# PUSH-BUTTON_ENCODER.net
KiCad netlist of a schematic drawn in Altium Designer
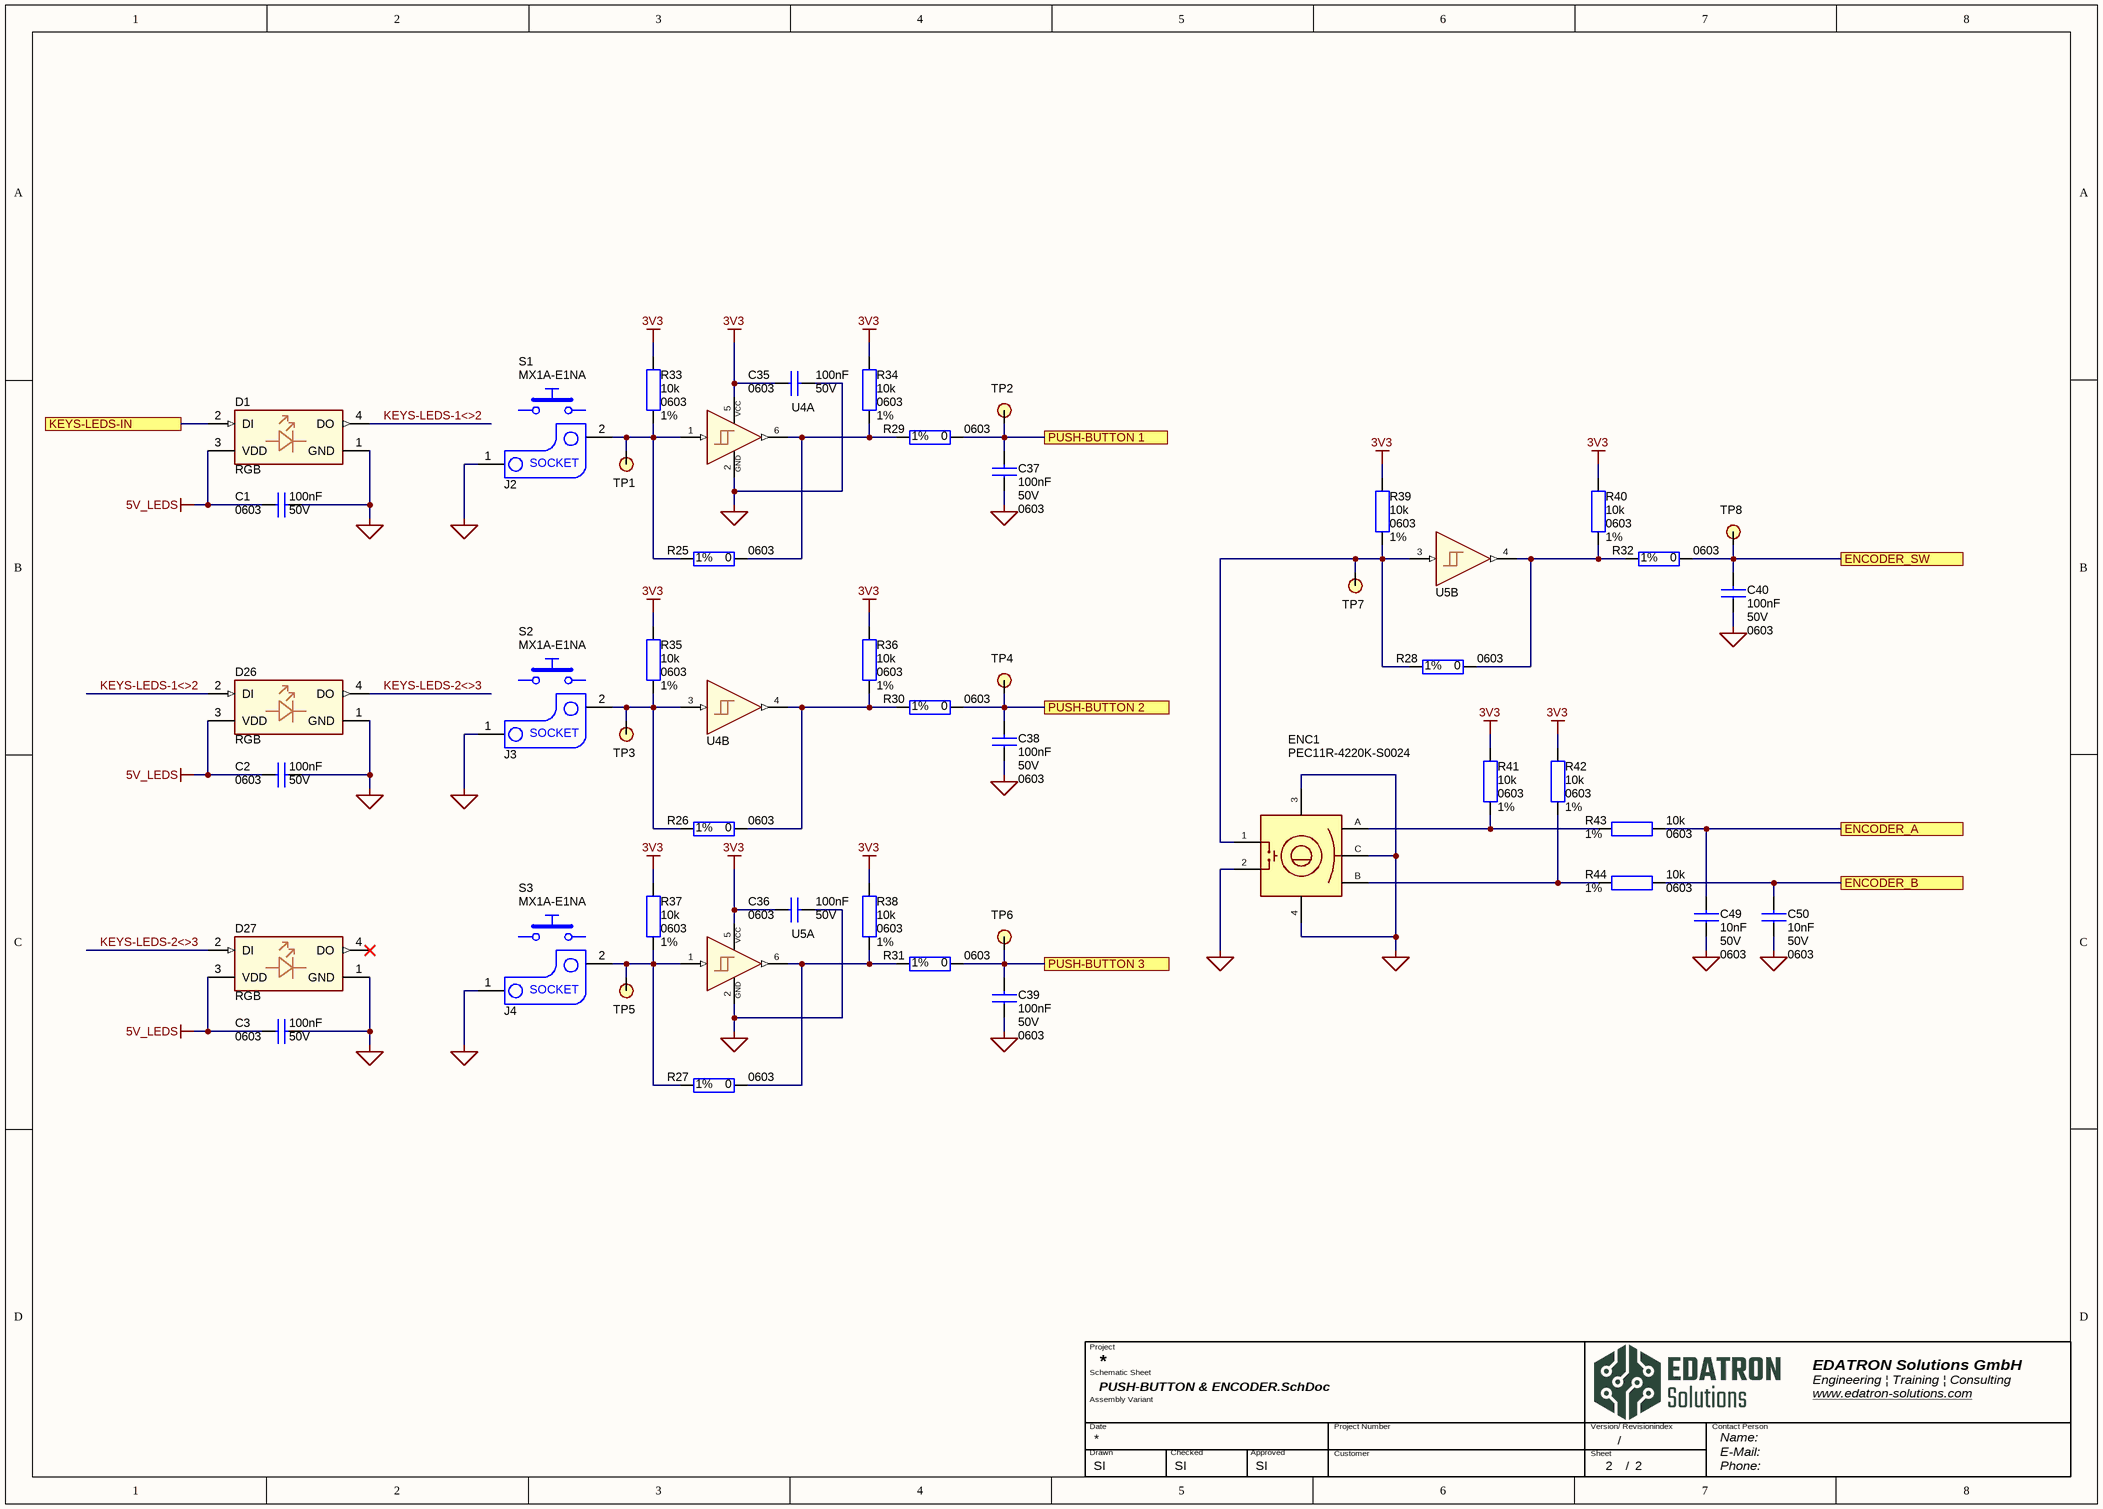
[diagram p0: PUSH-BUTTON & ENCODER.SchDoc]

(export (version "E")
  (design (tool "Eeschema 10.0.6"))
  (components
    (comp (ref "C1")
      (value "100nF")
      (footprint "CAPC0603X37L")
      (description "CAPACITOR 100 nF 0603 X7R 50V 10%")
      (fields
        (field (name "VOLTAGE") "50V")
        (field (name "MANUFACTURER 1 PART NUMBER") "C0603C104K5RACTU")
        (field (name "TOLERANCE") "10%")
        (field (name "CASE/PACKAGE") "0603")
        (field (name "COMMENT DESIGNER") "can be substituted same values other manufacturer")
      )
      (libsource (lib "EDATRON Solutions GmbH") (part "C"))
    )
    (comp (ref "C2")
      (value "100nF")
      (footprint "CAPC0603X37L")
      (description "CAPACITOR 100 nF 0603 X7R 50V 10%")
      (fields
        (field (name "VOLTAGE") "50V")
        (field (name "MANUFACTURER 1 PART NUMBER") "C0603C104K5RACTU")
        (field (name "TOLERANCE") "10%")
        (field (name "CASE/PACKAGE") "0603")
        (field (name "COMMENT DESIGNER") "can be substituted same values other manufacturer")
      )
      (libsource (lib "EDATRON Solutions GmbH") (part "C"))
    )
    (comp (ref "C3")
      (value "100nF")
      (footprint "CAPC0603X37L")
      (description "CAPACITOR 100 nF 0603 X7R 50V 10%")
      (fields
        (field (name "VOLTAGE") "50V")
        (field (name "MANUFACTURER 1 PART NUMBER") "C0603C104K5RACTU")
        (field (name "TOLERANCE") "10%")
        (field (name "CASE/PACKAGE") "0603")
        (field (name "COMMENT DESIGNER") "can be substituted same values other manufacturer")
      )
      (libsource (lib "EDATRON Solutions GmbH") (part "C"))
    )
    (comp (ref "C35")
      (value "100nF")
      (footprint "CAPC0603X37L")
      (description "CAPACITOR 100 nF 0603 X7R 50V 10%")
      (fields
        (field (name "VOLTAGE") "50V")
        (field (name "MANUFACTURER 1 PART NUMBER") "C0603C104K5RACTU")
        (field (name "TOLERANCE") "10%")
        (field (name "CASE/PACKAGE") "0603")
        (field (name "COMMENT DESIGNER") "can be substituted same values other manufacturer")
      )
      (libsource (lib "EDATRON Solutions GmbH") (part "C"))
    )
    (comp (ref "C36")
      (value "100nF")
      (footprint "CAPC0603X37L")
      (description "CAPACITOR 100 nF 0603 X7R 50V 10%")
      (fields
        (field (name "VOLTAGE") "50V")
        (field (name "MANUFACTURER 1 PART NUMBER") "C0603C104K5RACTU")
        (field (name "TOLERANCE") "10%")
        (field (name "CASE/PACKAGE") "0603")
        (field (name "COMMENT DESIGNER") "can be substituted same values other manufacturer")
      )
      (libsource (lib "EDATRON Solutions GmbH") (part "C"))
    )
    (comp (ref "C37")
      (value "100nF")
      (footprint "CAPC0603X37L")
      (description "CAPACITOR 100 nF 0603 X7R 50V 10%")
      (fields
        (field (name "VOLTAGE") "50V")
        (field (name "MANUFACTURER 1 PART NUMBER") "C0603C104K5RACTU")
        (field (name "TOLERANCE") "10%")
        (field (name "CASE/PACKAGE") "0603")
        (field (name "COMMENT DESIGNER") "can be substituted same values other manufacturer")
      )
      (libsource (lib "EDATRON Solutions GmbH") (part "C"))
    )
    (comp (ref "C38")
      (value "100nF")
      (footprint "CAPC0603X37L")
      (description "CAPACITOR 100 nF 0603 X7R 50V 10%")
      (fields
        (field (name "VOLTAGE") "50V")
        (field (name "MANUFACTURER 1 PART NUMBER") "C0603C104K5RACTU")
        (field (name "TOLERANCE") "10%")
        (field (name "CASE/PACKAGE") "0603")
        (field (name "COMMENT DESIGNER") "can be substituted same values other manufacturer")
      )
      (libsource (lib "EDATRON Solutions GmbH") (part "C"))
    )
    (comp (ref "C39")
      (value "100nF")
      (footprint "CAPC0603X37L")
      (description "CAPACITOR 100 nF 0603 X7R 50V 10%")
      (fields
        (field (name "VOLTAGE") "50V")
        (field (name "MANUFACTURER 1 PART NUMBER") "C0603C104K5RACTU")
        (field (name "TOLERANCE") "10%")
        (field (name "CASE/PACKAGE") "0603")
        (field (name "COMMENT DESIGNER") "can be substituted same values other manufacturer")
      )
      (libsource (lib "EDATRON Solutions GmbH") (part "C"))
    )
    (comp (ref "C40")
      (value "100nF")
      (footprint "CAPC0603X37L")
      (description "CAPACITOR 100 nF 0603 X7R 50V 10%")
      (fields
        (field (name "VOLTAGE") "50V")
        (field (name "MANUFACTURER 1 PART NUMBER") "C0603C104K5RACTU")
        (field (name "TOLERANCE") "10%")
        (field (name "CASE/PACKAGE") "0603")
        (field (name "COMMENT DESIGNER") "can be substituted same values other manufacturer")
      )
      (libsource (lib "EDATRON Solutions GmbH") (part "C"))
    )
    (comp (ref "C49")
      (value "10nF")
      (footprint "CAPC0603X37L")
      (description "CAPACITOR 10 nF 0603 X7R 50V 10%")
      (fields
        (field (name "VOLTAGE") "50V")
        (field (name "MANUFACTURER 1 PART NUMBER") "C0603C103K5RACTU")
        (field (name "TOLERANCE") "10%")
        (field (name "CASE/PACKAGE") "0603")
        (field (name "COMMENT DESIGNER") "can be substituted same values other manufacturer")
      )
      (libsource (lib "EDATRON Solutions GmbH") (part "C"))
    )
    (comp (ref "C50")
      (value "10nF")
      (footprint "CAPC0603X37L")
      (description "CAPACITOR 10 nF 0603 X7R 50V 10%")
      (fields
        (field (name "VOLTAGE") "50V")
        (field (name "MANUFACTURER 1 PART NUMBER") "C0603C103K5RACTU")
        (field (name "TOLERANCE") "10%")
        (field (name "CASE/PACKAGE") "0603")
        (field (name "COMMENT DESIGNER") "can be substituted same values other manufacturer")
      )
      (libsource (lib "EDATRON Solutions GmbH") (part "C"))
    )
    (comp (ref "D1")
      (value "SK6812MINI-E-012")
      (footprint "OPSCO_SK6812MINI-E-012")
      (description "SMD RGB LEDs(Built-in IC) ROHS  - Reverse Mount")
      (fields (field (name "COLOR") "RGB") (field (name "VOLTAGE") "5V"))
      (libsource (lib "EDATRON Solutions GmbH") (part "RGB-LED (Built-in IC) - Opsco"))
    )
    (comp (ref "D26")
      (value "SK6812MINI-E-012")
      (footprint "OPSCO_SK6812MINI-E-012")
      (description "SMD RGB LEDs(Built-in IC) ROHS  - Reverse Mount")
      (fields (field (name "COLOR") "RGB") (field (name "VOLTAGE") "5V"))
      (libsource (lib "EDATRON Solutions GmbH") (part "RGB-LED (Built-in IC) - Opsco"))
    )
    (comp (ref "D27")
      (value "SK6812MINI-E-012")
      (footprint "OPSCO_SK6812MINI-E-012")
      (description "SMD RGB LEDs(Built-in IC) ROHS  - Reverse Mount")
      (fields (field (name "COLOR") "RGB") (field (name "VOLTAGE") "5V"))
      (libsource (lib "EDATRON Solutions GmbH") (part "RGB-LED (Built-in IC) - Opsco"))
    )
    (comp (ref "ENC1")
      (value "PEC11R-4220K-S0024")
      (footprint "PEC11R-4220K-S0024")
      (description "Rotary Position Encoder")
      (fields (field (name "VOLTAGE") "5V"))
      (libsource (lib "EDATRON Solutions GmbH") (part "PEC11R"))
    )
    (comp (ref "J2")
      (value "CPG151101S11-16")
      (footprint "KAILH_CPG151101S11-16")
      (description "Socket PG1511 KeySwitches Contact Ⅲ (MX Series Cherry)")
      (fields (field (name "VOLTAGE") "12V") (field (name "COMMENT DESIGNER") "Clone of Cerry MX Series"))
      (libsource (lib "EDATRON Solutions GmbH") (part "Socket CPG151101S11-16"))
    )
    (comp (ref "J3")
      (value "CPG151101S11-16")
      (footprint "KAILH_CPG151101S11-16")
      (description "Socket PG1511 KeySwitches Contact Ⅲ (MX Series Cherry)")
      (fields (field (name "VOLTAGE") "12V") (field (name "COMMENT DESIGNER") "Clone of Cerry MX Series"))
      (libsource (lib "EDATRON Solutions GmbH") (part "Socket CPG151101S11-16"))
    )
    (comp (ref "J4")
      (value "CPG151101S11-16")
      (footprint "KAILH_CPG151101S11-16")
      (description "Socket PG1511 KeySwitches Contact Ⅲ (MX Series Cherry)")
      (fields (field (name "VOLTAGE") "12V") (field (name "COMMENT DESIGNER") "Clone of Cerry MX Series"))
      (libsource (lib "EDATRON Solutions GmbH") (part "Socket CPG151101S11-16"))
    )
    (comp (ref "R25")
      (value "0")
      (footprint "RESC0603X21L")
      (description "RESISTOR 0R 1% 0603 100mW")
      (fields
        (field (name "MANUFACTURER 1 PART NUMBER") "RC0603FR-070RL")
        (field (name "CASE/PACKAGE") "0603")
        (field (name "POWER") "100mW")
        (field (name "TOLERANCE") "1%")
        (field (name "COMMENT DESIGNER") "can be substituted same values other manufacturers")
      )
      (libsource (lib "") (part "R_1"))
    )
    (comp (ref "R26")
      (value "0")
      (footprint "RESC0603X21L")
      (description "RESISTOR 0R 1% 0603 100mW")
      (fields
        (field (name "MANUFACTURER 1 PART NUMBER") "RC0603FR-070RL")
        (field (name "CASE/PACKAGE") "0603")
        (field (name "POWER") "100mW")
        (field (name "TOLERANCE") "1%")
        (field (name "COMMENT DESIGNER") "can be substituted same values other manufacturers")
      )
      (libsource (lib "") (part "R_1"))
    )
    (comp (ref "R27")
      (value "0")
      (footprint "RESC0603X21L")
      (description "RESISTOR 0R 1% 0603 100mW")
      (fields
        (field (name "MANUFACTURER 1 PART NUMBER") "RC0603FR-070RL")
        (field (name "CASE/PACKAGE") "0603")
        (field (name "POWER") "100mW")
        (field (name "TOLERANCE") "1%")
        (field (name "COMMENT DESIGNER") "can be substituted same values other manufacturers")
      )
      (libsource (lib "") (part "R_1"))
    )
    (comp (ref "R28")
      (value "0")
      (footprint "RESC0603X21L")
      (description "RESISTOR 0R 1% 0603 100mW")
      (fields
        (field (name "MANUFACTURER 1 PART NUMBER") "RC0603FR-070RL")
        (field (name "CASE/PACKAGE") "0603")
        (field (name "POWER") "100mW")
        (field (name "TOLERANCE") "1%")
        (field (name "COMMENT DESIGNER") "can be substituted same values other manufacturers")
      )
      (libsource (lib "") (part "R_1"))
    )
    (comp (ref "R29")
      (value "0")
      (footprint "RESC0603X21L")
      (description "RESISTOR 0R 1% 0603 100mW")
      (fields
        (field (name "MANUFACTURER 1 PART NUMBER") "RC0603FR-070RL")
        (field (name "CASE/PACKAGE") "0603")
        (field (name "POWER") "100mW")
        (field (name "TOLERANCE") "1%")
        (field (name "COMMENT DESIGNER") "can be substituted same values other manufacturers")
      )
      (libsource (lib "") (part "R_1"))
    )
    (comp (ref "R30")
      (value "0")
      (footprint "RESC0603X21L")
      (description "RESISTOR 0R 1% 0603 100mW")
      (fields
        (field (name "MANUFACTURER 1 PART NUMBER") "RC0603FR-070RL")
        (field (name "CASE/PACKAGE") "0603")
        (field (name "POWER") "100mW")
        (field (name "TOLERANCE") "1%")
        (field (name "COMMENT DESIGNER") "can be substituted same values other manufacturers")
      )
      (libsource (lib "") (part "R_1"))
    )
    (comp (ref "R31")
      (value "0")
      (footprint "RESC0603X21L")
      (description "RESISTOR 0R 1% 0603 100mW")
      (fields
        (field (name "MANUFACTURER 1 PART NUMBER") "RC0603FR-070RL")
        (field (name "CASE/PACKAGE") "0603")
        (field (name "POWER") "100mW")
        (field (name "TOLERANCE") "1%")
        (field (name "COMMENT DESIGNER") "can be substituted same values other manufacturers")
      )
      (libsource (lib "") (part "R_1"))
    )
    (comp (ref "R32")
      (value "0")
      (footprint "RESC0603X21L")
      (description "RESISTOR 0R 1% 0603 100mW")
      (fields
        (field (name "MANUFACTURER 1 PART NUMBER") "RC0603FR-070RL")
        (field (name "CASE/PACKAGE") "0603")
        (field (name "POWER") "100mW")
        (field (name "TOLERANCE") "1%")
        (field (name "COMMENT DESIGNER") "can be substituted same values other manufacturers")
      )
      (libsource (lib "") (part "R_1"))
    )
    (comp (ref "R33")
      (value "10k")
      (footprint "RESC0603X21L")
      (description "RESISTOR 33K 1% 0603 100mW")
      (fields
        (field (name "MANUFACTURER 1 PART NUMBER") "RC0603FR-0733KL")
        (field (name "POWER") "100mW")
        (field (name "CASE/PACKAGE") "0603")
        (field (name "TOLERANCE") "1%")
        (field (name "COMMENT DESIGNER") "can be substituted same values other manufacturers")
      )
      (libsource (lib "EDATRON Solutions GmbH") (part "R"))
    )
    (comp (ref "R34")
      (value "10k")
      (footprint "RESC0603X21L")
      (description "RESISTOR 33K 1% 0603 100mW")
      (fields
        (field (name "MANUFACTURER 1 PART NUMBER") "RC0603FR-0733KL")
        (field (name "POWER") "100mW")
        (field (name "CASE/PACKAGE") "0603")
        (field (name "TOLERANCE") "1%")
        (field (name "COMMENT DESIGNER") "can be substituted same values other manufacturers")
      )
      (libsource (lib "EDATRON Solutions GmbH") (part "R"))
    )
    (comp (ref "R35")
      (value "10k")
      (footprint "RESC0603X21L")
      (description "RESISTOR 33K 1% 0603 100mW")
      (fields
        (field (name "MANUFACTURER 1 PART NUMBER") "RC0603FR-0733KL")
        (field (name "POWER") "100mW")
        (field (name "CASE/PACKAGE") "0603")
        (field (name "TOLERANCE") "1%")
        (field (name "COMMENT DESIGNER") "can be substituted same values other manufacturers")
      )
      (libsource (lib "EDATRON Solutions GmbH") (part "R"))
    )
    (comp (ref "R36")
      (value "10k")
      (footprint "RESC0603X21L")
      (description "RESISTOR 33K 1% 0603 100mW")
      (fields
        (field (name "MANUFACTURER 1 PART NUMBER") "RC0603FR-0733KL")
        (field (name "POWER") "100mW")
        (field (name "CASE/PACKAGE") "0603")
        (field (name "TOLERANCE") "1%")
        (field (name "COMMENT DESIGNER") "can be substituted same values other manufacturers")
      )
      (libsource (lib "EDATRON Solutions GmbH") (part "R"))
    )
    (comp (ref "R37")
      (value "10k")
      (footprint "RESC0603X21L")
      (description "RESISTOR 33K 1% 0603 100mW")
      (fields
        (field (name "MANUFACTURER 1 PART NUMBER") "RC0603FR-0733KL")
        (field (name "POWER") "100mW")
        (field (name "CASE/PACKAGE") "0603")
        (field (name "TOLERANCE") "1%")
        (field (name "COMMENT DESIGNER") "can be substituted same values other manufacturers")
      )
      (libsource (lib "EDATRON Solutions GmbH") (part "R"))
    )
    (comp (ref "R38")
      (value "10k")
      (footprint "RESC0603X21L")
      (description "RESISTOR 33K 1% 0603 100mW")
      (fields
        (field (name "MANUFACTURER 1 PART NUMBER") "RC0603FR-0733KL")
        (field (name "POWER") "100mW")
        (field (name "CASE/PACKAGE") "0603")
        (field (name "TOLERANCE") "1%")
        (field (name "COMMENT DESIGNER") "can be substituted same values other manufacturers")
      )
      (libsource (lib "EDATRON Solutions GmbH") (part "R"))
    )
    (comp (ref "R39")
      (value "10k")
      (footprint "RESC0603X21L")
      (description "RESISTOR 33K 1% 0603 100mW")
      (fields
        (field (name "MANUFACTURER 1 PART NUMBER") "RC0603FR-0733KL")
        (field (name "POWER") "100mW")
        (field (name "CASE/PACKAGE") "0603")
        (field (name "TOLERANCE") "1%")
        (field (name "COMMENT DESIGNER") "can be substituted same values other manufacturers")
      )
      (libsource (lib "EDATRON Solutions GmbH") (part "R"))
    )
    (comp (ref "R40")
      (value "10k")
      (footprint "RESC0603X21L")
      (description "RESISTOR 33K 1% 0603 100mW")
      (fields
        (field (name "MANUFACTURER 1 PART NUMBER") "RC0603FR-0733KL")
        (field (name "POWER") "100mW")
        (field (name "CASE/PACKAGE") "0603")
        (field (name "TOLERANCE") "1%")
        (field (name "COMMENT DESIGNER") "can be substituted same values other manufacturers")
      )
      (libsource (lib "EDATRON Solutions GmbH") (part "R"))
    )
    (comp (ref "R41")
      (value "10k")
      (footprint "RESC0603X21L")
      (description "RESISTOR 33K 1% 0603 100mW")
      (fields
        (field (name "MANUFACTURER 1 PART NUMBER") "RC0603FR-0733KL")
        (field (name "POWER") "100mW")
        (field (name "CASE/PACKAGE") "0603")
        (field (name "TOLERANCE") "1%")
        (field (name "COMMENT DESIGNER") "can be substituted same values other manufacturers")
      )
      (libsource (lib "EDATRON Solutions GmbH") (part "R"))
    )
    (comp (ref "R42")
      (value "10k")
      (footprint "RESC0603X21L")
      (description "RESISTOR 33K 1% 0603 100mW")
      (fields
        (field (name "MANUFACTURER 1 PART NUMBER") "RC0603FR-0733KL")
        (field (name "POWER") "100mW")
        (field (name "CASE/PACKAGE") "0603")
        (field (name "TOLERANCE") "1%")
        (field (name "COMMENT DESIGNER") "can be substituted same values other manufacturers")
      )
      (libsource (lib "EDATRON Solutions GmbH") (part "R"))
    )
    (comp (ref "R43")
      (value "10k")
      (footprint "RESC0603X21L")
      (description "RESISTOR 33K 1% 0603 100mW")
      (fields
        (field (name "MANUFACTURER 1 PART NUMBER") "RC0603FR-0733KL")
        (field (name "POWER") "100mW")
        (field (name "CASE/PACKAGE") "0603")
        (field (name "TOLERANCE") "1%")
        (field (name "COMMENT DESIGNER") "can be substituted same values other manufacturers")
      )
      (libsource (lib "") (part "R_1"))
    )
    (comp (ref "R44")
      (value "10k")
      (footprint "RESC0603X21L")
      (description "RESISTOR 33K 1% 0603 100mW")
      (fields
        (field (name "MANUFACTURER 1 PART NUMBER") "RC0603FR-0733KL")
        (field (name "POWER") "100mW")
        (field (name "CASE/PACKAGE") "0603")
        (field (name "TOLERANCE") "1%")
        (field (name "COMMENT DESIGNER") "can be substituted same values other manufacturers")
      )
      (libsource (lib "") (part "R_1"))
    )
    (comp (ref "S1")
      (value "MX1A-E1NA")
      (footprint "KAILH_SWITCH_MX_COMPATIBEL")
      (description "Cherry MX1A-E1NA - Schnappbefestigung im Rahmen")
      (fields
        (field (name "VOLTAGE") "12V")
        (field (name "COMMENT DESIGNER") "can be substituted by other Switches form Kailh or Cherry MX Series")
      )
      (libsource (lib "EDATRON Solutions GmbH") (part "PUSH BUTTON (Mechanical)"))
    )
    (comp (ref "S2")
      (value "MX1A-E1NA")
      (footprint "KAILH_SWITCH_MX_COMPATIBEL")
      (description "Cherry MX1A-E1NA - Schnappbefestigung im Rahmen")
      (fields
        (field (name "VOLTAGE") "12V")
        (field (name "COMMENT DESIGNER") "can be substituted by other Switches form Kailh or Cherry MX Series")
      )
      (libsource (lib "EDATRON Solutions GmbH") (part "PUSH BUTTON (Mechanical)"))
    )
    (comp (ref "S3")
      (value "MX1A-E1NA")
      (footprint "KAILH_SWITCH_MX_COMPATIBEL")
      (description "Cherry MX1A-E1NA - Schnappbefestigung im Rahmen")
      (fields
        (field (name "VOLTAGE") "12V")
        (field (name "COMMENT DESIGNER") "can be substituted by other Switches form Kailh or Cherry MX Series")
      )
      (libsource (lib "EDATRON Solutions GmbH") (part "PUSH BUTTON (Mechanical)"))
    )
    (comp (ref "TP1")
      (value "SMD-Testpoint")
      (footprint "SMT-1.00mm Testpoint")
      (description "SMT-TESTPOINT")
      (libsource (lib "EDATRON Solutions GmbH") (part "Testpoint"))
    )
    (comp (ref "TP2")
      (value "SMD-Testpoint")
      (footprint "SMT-1.00mm Testpoint")
      (description "SMT-TESTPOINT")
      (libsource (lib "EDATRON Solutions GmbH") (part "Testpoint"))
    )
    (comp (ref "TP3")
      (value "SMD-Testpoint")
      (footprint "SMT-1.00mm Testpoint")
      (description "SMT-TESTPOINT")
      (libsource (lib "EDATRON Solutions GmbH") (part "Testpoint"))
    )
    (comp (ref "TP4")
      (value "SMD-Testpoint")
      (footprint "SMT-1.00mm Testpoint")
      (description "SMT-TESTPOINT")
      (libsource (lib "EDATRON Solutions GmbH") (part "Testpoint"))
    )
    (comp (ref "TP5")
      (value "SMD-Testpoint")
      (footprint "SMT-1.00mm Testpoint")
      (description "SMT-TESTPOINT")
      (libsource (lib "EDATRON Solutions GmbH") (part "Testpoint"))
    )
    (comp (ref "TP6")
      (value "SMD-Testpoint")
      (footprint "SMT-1.00mm Testpoint")
      (description "SMT-TESTPOINT")
      (libsource (lib "EDATRON Solutions GmbH") (part "Testpoint"))
    )
    (comp (ref "TP7")
      (value "SMD-Testpoint")
      (footprint "SMT-1.00mm Testpoint")
      (description "SMT-TESTPOINT")
      (libsource (lib "EDATRON Solutions GmbH") (part "Testpoint"))
    )
    (comp (ref "TP8")
      (value "SMD-Testpoint")
      (footprint "SMT-1.00mm Testpoint")
      (description "SMT-TESTPOINT")
      (libsource (lib "EDATRON Solutions GmbH") (part "Testpoint"))
    )
    (comp (ref "U4")
      (value "SN74LVC2G17DCKR")
      (footprint "SOT23-6P65_200X210X110L36X22L")
      (description "SN74LVC2G17 Dual Schmitt-Trigger Buffer")
      (libsource (lib "EDATRON Solutions GmbH") (part "Schmitt Trigger SN74LVC2G17"))
    )
    (comp (ref "U5")
      (value "SN74LVC2G17DCKR")
      (footprint "SOT23-6P65_200X210X110L36X22L")
      (description "SN74LVC2G17 Dual Schmitt-Trigger Buffer")
      (libsource (lib "EDATRON Solutions GmbH") (part "Schmitt Trigger SN74LVC2G17"))
    )
  )
  (nets
    (net (code "2") (name "/ENCODER_A") (class "Default")
      (node (ref "C49") (pin "2") (pinfunction "2_2") (pintype "passive"))
      (node (ref "R43") (pin "2") (pinfunction "2_2") (pintype "passive"))
    )
    (net (code "3") (name "/ENCODER_B") (class "Default")
      (node (ref "C50") (pin "2") (pinfunction "2_2") (pintype "passive"))
      (node (ref "R44") (pin "2") (pinfunction "2_2") (pintype "passive"))
    )
    (net (code "4") (name "/ENCODER_SW") (class "Default")
      (node (ref "C40") (pin "2") (pinfunction "2_2") (pintype "passive"))
      (node (ref "R32") (pin "2") (pinfunction "2_2") (pintype "passive"))
      (node (ref "TP8") (pin "1") (pinfunction "1_1") (pintype "passive"))
    )
    (net (code "5") (name "/KEYS-LEDS-1<>2") (class "Default")
      (node (ref "D1") (pin "4") (pinfunction "DO_4") (pintype "output"))
      (node (ref "D26") (pin "2") (pinfunction "DI_2") (pintype "input"))
    )
    (net (code "6") (name "/KEYS-LEDS-2<>3") (class "Default")
      (node (ref "D26") (pin "4") (pinfunction "DO_4") (pintype "output"))
      (node (ref "D27") (pin "2") (pinfunction "DI_2") (pintype "input"))
    )
    (net (code "7") (name "/KEYS-LEDS-IN") (class "Default")
      (node (ref "D1") (pin "2") (pinfunction "DI_2") (pintype "input"))
    )
    (net (code "8") (name "/PUSH-BUTTON 1") (class "Default")
      (node (ref "C37") (pin "2") (pinfunction "2_2") (pintype "passive"))
      (node (ref "R29") (pin "2") (pinfunction "2_2") (pintype "passive"))
      (node (ref "TP2") (pin "1") (pinfunction "1_1") (pintype "passive"))
    )
    (net (code "9") (name "/PUSH-BUTTON 2") (class "Default")
      (node (ref "C38") (pin "2") (pinfunction "2_2") (pintype "passive"))
      (node (ref "R30") (pin "2") (pinfunction "2_2") (pintype "passive"))
      (node (ref "TP4") (pin "1") (pinfunction "1_1") (pintype "passive"))
    )
    (net (code "10") (name "/PUSH-BUTTON 3") (class "Default")
      (node (ref "C39") (pin "2") (pinfunction "2_2") (pintype "passive"))
      (node (ref "R31") (pin "2") (pinfunction "2_2") (pintype "passive"))
      (node (ref "TP6") (pin "1") (pinfunction "1_1") (pintype "passive"))
    )
    (net (code "11") (name "3V3") (class "Default")
      (node (ref "C35") (pin "1") (pinfunction "1_1") (pintype "passive"))
      (node (ref "C36") (pin "1") (pinfunction "1_1") (pintype "passive"))
      (node (ref "R33") (pin "1") (pinfunction "1_1") (pintype "passive"))
      (node (ref "R34") (pin "1") (pinfunction "1_1") (pintype "passive"))
      (node (ref "R35") (pin "1") (pinfunction "1_1") (pintype "passive"))
      (node (ref "R36") (pin "1") (pinfunction "1_1") (pintype "passive"))
      (node (ref "R37") (pin "1") (pinfunction "1_1") (pintype "passive"))
      (node (ref "R38") (pin "1") (pinfunction "1_1") (pintype "passive"))
      (node (ref "R39") (pin "1") (pinfunction "1_1") (pintype "passive"))
      (node (ref "R40") (pin "1") (pinfunction "1_1") (pintype "passive"))
      (node (ref "R41") (pin "1") (pinfunction "1_1") (pintype "passive"))
      (node (ref "R42") (pin "1") (pinfunction "1_1") (pintype "passive"))
      (node (ref "U4") (pin "5") (pinfunction "VCC_5") (pintype "power_in"))
      (node (ref "U5") (pin "5") (pinfunction "VCC_5") (pintype "power_in"))
    )
    (net (code "12") (name "5V_LEDS") (class "Default")
      (node (ref "C1") (pin "1") (pinfunction "1_1") (pintype "passive"))
      (node (ref "C2") (pin "1") (pinfunction "1_1") (pintype "passive"))
      (node (ref "C3") (pin "1") (pinfunction "1_1") (pintype "passive"))
      (node (ref "D1") (pin "3") (pinfunction "VDD_3") (pintype "passive"))
      (node (ref "D26") (pin "3") (pinfunction "VDD_3") (pintype "passive"))
      (node (ref "D27") (pin "3") (pinfunction "VDD_3") (pintype "passive"))
    )
    (net (code "13") (name "GND") (class "Default")
      (node (ref "C1") (pin "2") (pinfunction "2_2") (pintype "passive"))
      (node (ref "C2") (pin "2") (pinfunction "2_2") (pintype "passive"))
      (node (ref "C3") (pin "2") (pinfunction "2_2") (pintype "passive"))
      (node (ref "C35") (pin "2") (pinfunction "2_2") (pintype "passive"))
      (node (ref "C36") (pin "2") (pinfunction "2_2") (pintype "passive"))
      (node (ref "C37") (pin "1") (pinfunction "1_1") (pintype "passive"))
      (node (ref "C38") (pin "1") (pinfunction "1_1") (pintype "passive"))
      (node (ref "C39") (pin "1") (pinfunction "1_1") (pintype "passive"))
      (node (ref "C40") (pin "1") (pinfunction "1_1") (pintype "passive"))
      (node (ref "C49") (pin "1") (pinfunction "1_1") (pintype "passive"))
      (node (ref "C50") (pin "1") (pinfunction "1_1") (pintype "passive"))
      (node (ref "D1") (pin "1") (pinfunction "GND_1") (pintype "passive"))
      (node (ref "D26") (pin "1") (pinfunction "GND_1") (pintype "passive"))
      (node (ref "D27") (pin "1") (pinfunction "GND_1") (pintype "passive"))
      (node (ref "ENC1") (pin "2") (pinfunction "2_2") (pintype "passive"))
      (node (ref "ENC1") (pin "3") (pinfunction "MNT_1_3") (pintype "passive"))
      (node (ref "ENC1") (pin "4") (pinfunction "MNT_2_4") (pintype "passive"))
      (node (ref "ENC1") (pin "C") (pinfunction "COMMON_C") (pintype "passive"))
      (node (ref "J2") (pin "1") (pinfunction "1_1") (pintype "passive"))
      (node (ref "J3") (pin "1") (pinfunction "1_1") (pintype "passive"))
      (node (ref "J4") (pin "1") (pinfunction "1_1") (pintype "passive"))
      (node (ref "U4") (pin "2") (pinfunction "GND_2") (pintype "power_in"))
      (node (ref "U5") (pin "2") (pinfunction "GND_2") (pintype "power_in"))
    )
    (net (code "14") (name "Net-(ENC1-CHANNEL_A)") (class "Default")
      (node (ref "ENC1") (pin "A") (pinfunction "CHANNEL_A_A") (pintype "passive"))
      (node (ref "R41") (pin "2") (pinfunction "2_2") (pintype "passive"))
      (node (ref "R43") (pin "1") (pinfunction "1_1") (pintype "passive"))
    )
    (net (code "15") (name "Net-(ENC1-CHANNEL_B)") (class "Default")
      (node (ref "ENC1") (pin "B") (pinfunction "CHANNEL_B_B") (pintype "passive"))
      (node (ref "R42") (pin "2") (pinfunction "2_2") (pintype "passive"))
      (node (ref "R44") (pin "1") (pinfunction "1_1") (pintype "passive"))
    )
    (net (code "16") (name "Net-(U4A-1A)") (class "Default")
      (node (ref "J2") (pin "2") (pinfunction "2_2") (pintype "passive"))
      (node (ref "R25") (pin "1") (pinfunction "1_1") (pintype "passive"))
      (node (ref "R33") (pin "2") (pinfunction "2_2") (pintype "passive"))
      (node (ref "TP1") (pin "1") (pinfunction "1_1") (pintype "passive"))
      (node (ref "U4") (pin "1") (pinfunction "1A_1") (pintype "input"))
    )
    (net (code "17") (name "Net-(U4A-1Y)") (class "Default")
      (node (ref "R25") (pin "2") (pinfunction "2_2") (pintype "passive"))
      (node (ref "R29") (pin "1") (pinfunction "1_1") (pintype "passive"))
      (node (ref "R34") (pin "2") (pinfunction "2_2") (pintype "passive"))
      (node (ref "U4") (pin "6") (pinfunction "1Y_6") (pintype "output"))
    )
    (net (code "18") (name "Net-(U4B-2A)") (class "Default")
      (node (ref "J3") (pin "2") (pinfunction "2_2") (pintype "passive"))
      (node (ref "R26") (pin "1") (pinfunction "1_1") (pintype "passive"))
      (node (ref "R35") (pin "2") (pinfunction "2_2") (pintype "passive"))
      (node (ref "TP3") (pin "1") (pinfunction "1_1") (pintype "passive"))
      (node (ref "U4") (pin "3") (pinfunction "2A_3") (pintype "input"))
    )
    (net (code "19") (name "Net-(U4B-2Y)") (class "Default")
      (node (ref "R26") (pin "2") (pinfunction "2_2") (pintype "passive"))
      (node (ref "R30") (pin "1") (pinfunction "1_1") (pintype "passive"))
      (node (ref "R36") (pin "2") (pinfunction "2_2") (pintype "passive"))
      (node (ref "U4") (pin "4") (pinfunction "2Y_4") (pintype "output"))
    )
    (net (code "20") (name "Net-(U5A-1A)") (class "Default")
      (node (ref "J4") (pin "2") (pinfunction "2_2") (pintype "passive"))
      (node (ref "R27") (pin "1") (pinfunction "1_1") (pintype "passive"))
      (node (ref "R37") (pin "2") (pinfunction "2_2") (pintype "passive"))
      (node (ref "TP5") (pin "1") (pinfunction "1_1") (pintype "passive"))
      (node (ref "U5") (pin "1") (pinfunction "1A_1") (pintype "input"))
    )
    (net (code "21") (name "Net-(U5A-1Y)") (class "Default")
      (node (ref "R27") (pin "2") (pinfunction "2_2") (pintype "passive"))
      (node (ref "R31") (pin "1") (pinfunction "1_1") (pintype "passive"))
      (node (ref "R38") (pin "2") (pinfunction "2_2") (pintype "passive"))
      (node (ref "U5") (pin "6") (pinfunction "1Y_6") (pintype "output"))
    )
    (net (code "22") (name "Net-(U5B-2A)") (class "Default")
      (node (ref "ENC1") (pin "1") (pinfunction "1_1") (pintype "passive"))
      (node (ref "R28") (pin "1") (pinfunction "1_1") (pintype "passive"))
      (node (ref "R39") (pin "2") (pinfunction "2_2") (pintype "passive"))
      (node (ref "TP7") (pin "1") (pinfunction "1_1") (pintype "passive"))
      (node (ref "U5") (pin "3") (pinfunction "2A_3") (pintype "input"))
    )
    (net (code "23") (name "Net-(U5B-2Y)") (class "Default")
      (node (ref "R28") (pin "2") (pinfunction "2_2") (pintype "passive"))
      (node (ref "R32") (pin "1") (pinfunction "1_1") (pintype "passive"))
      (node (ref "R40") (pin "2") (pinfunction "2_2") (pintype "passive"))
      (node (ref "U5") (pin "4") (pinfunction "2Y_4") (pintype "output"))
    )
    (net (code "24") (name "unconnected-(D27-DO-Pad4)") (class "Default")
      (node (ref "D27") (pin "4") (pinfunction "DO_4") (pintype "output+no_connect"))
    )
  )
)
